# ModuleCarrier-Laird-BL652-v1_0_0.net
KiCad netlist of a schematic drawn in EAGLE
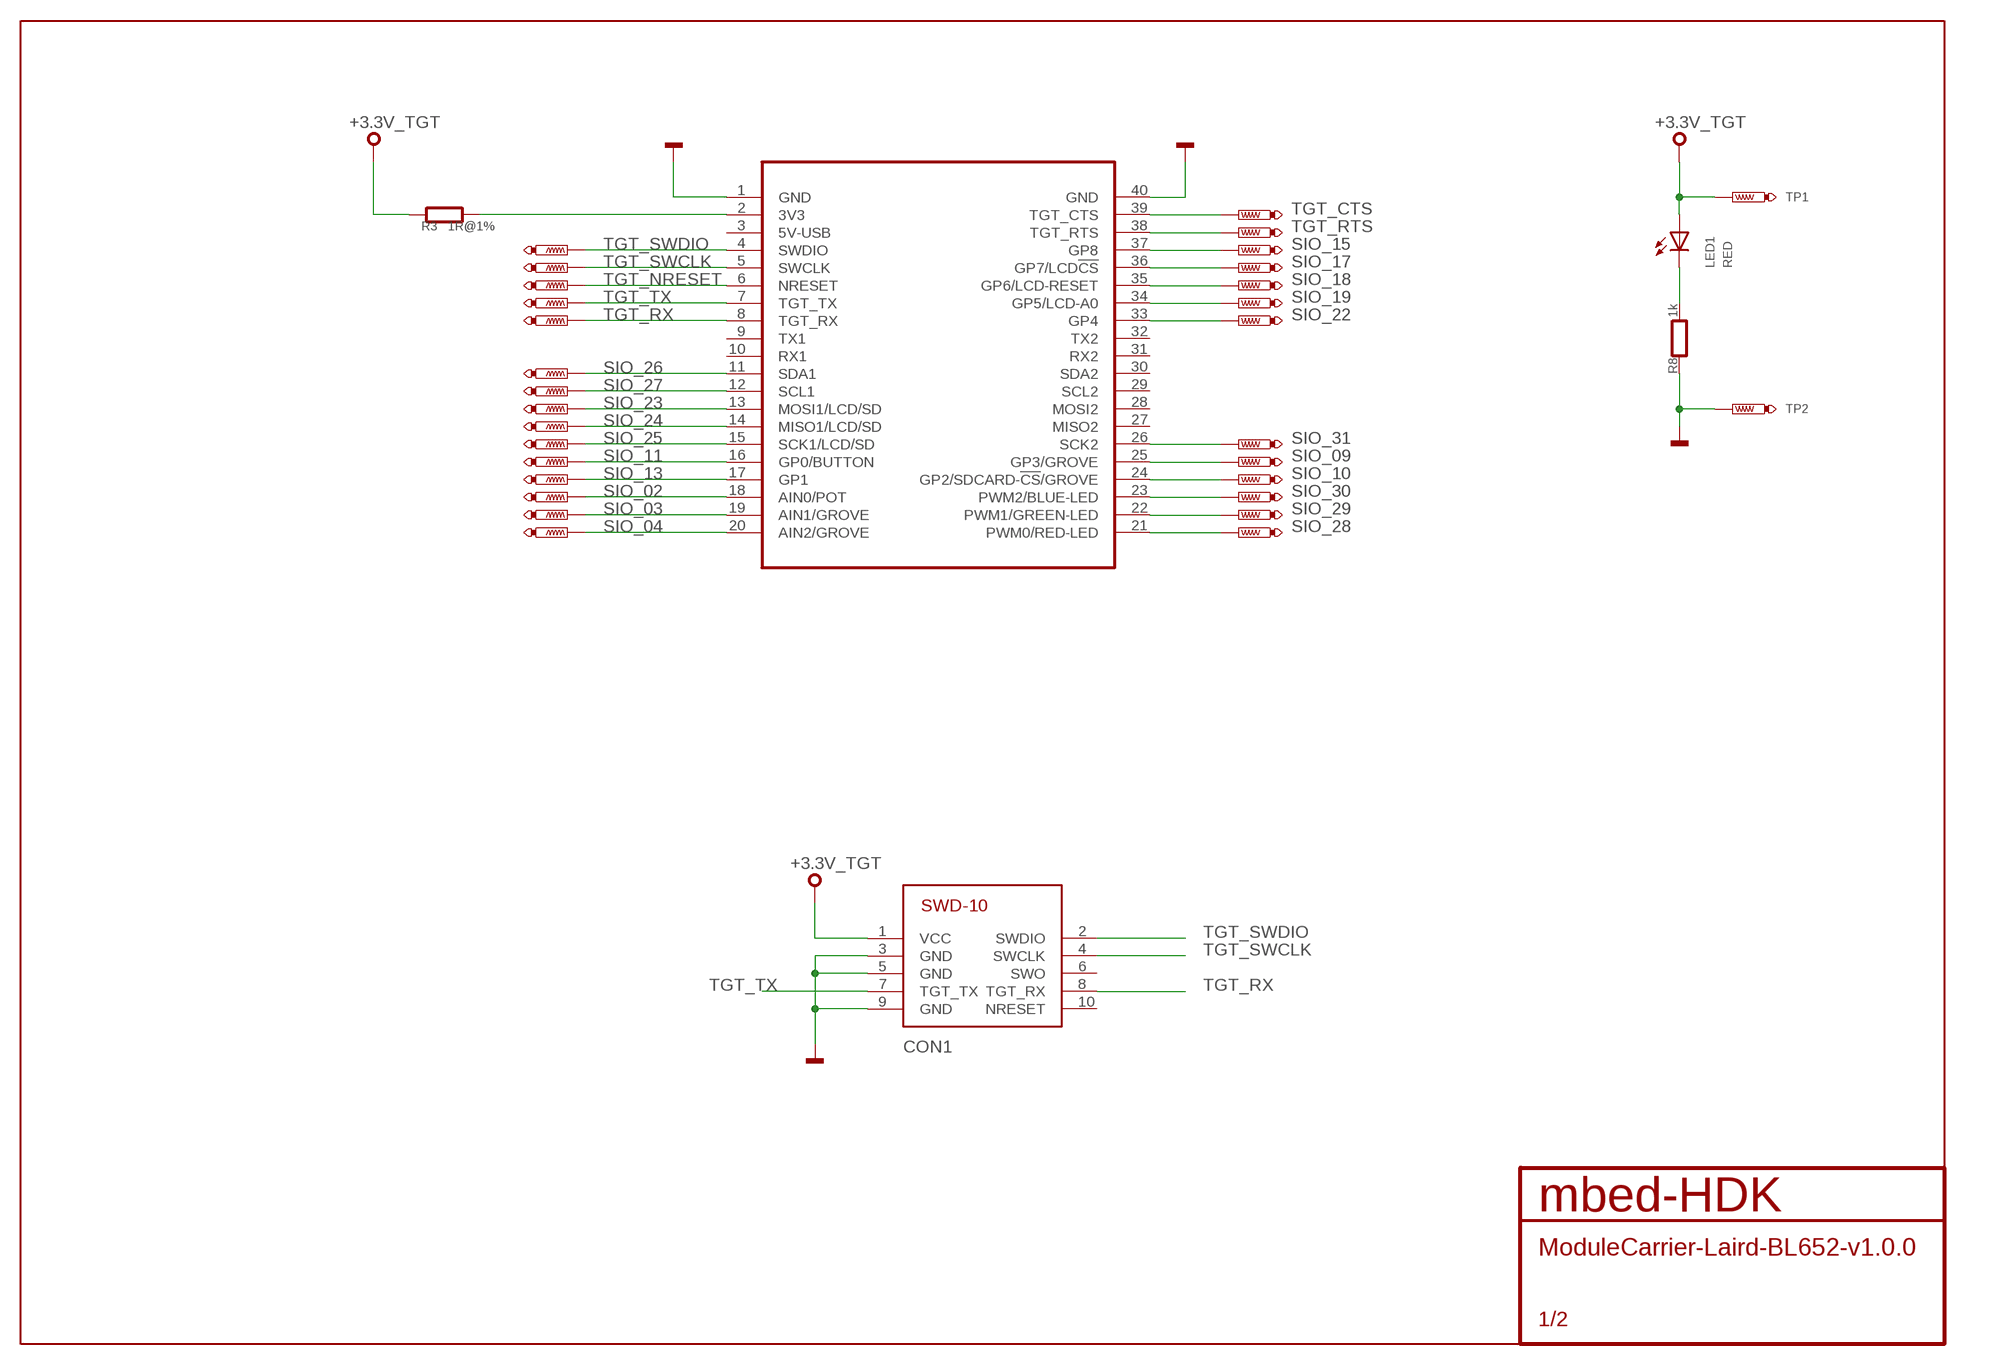
[diagram p0: schematic, sheet 1]
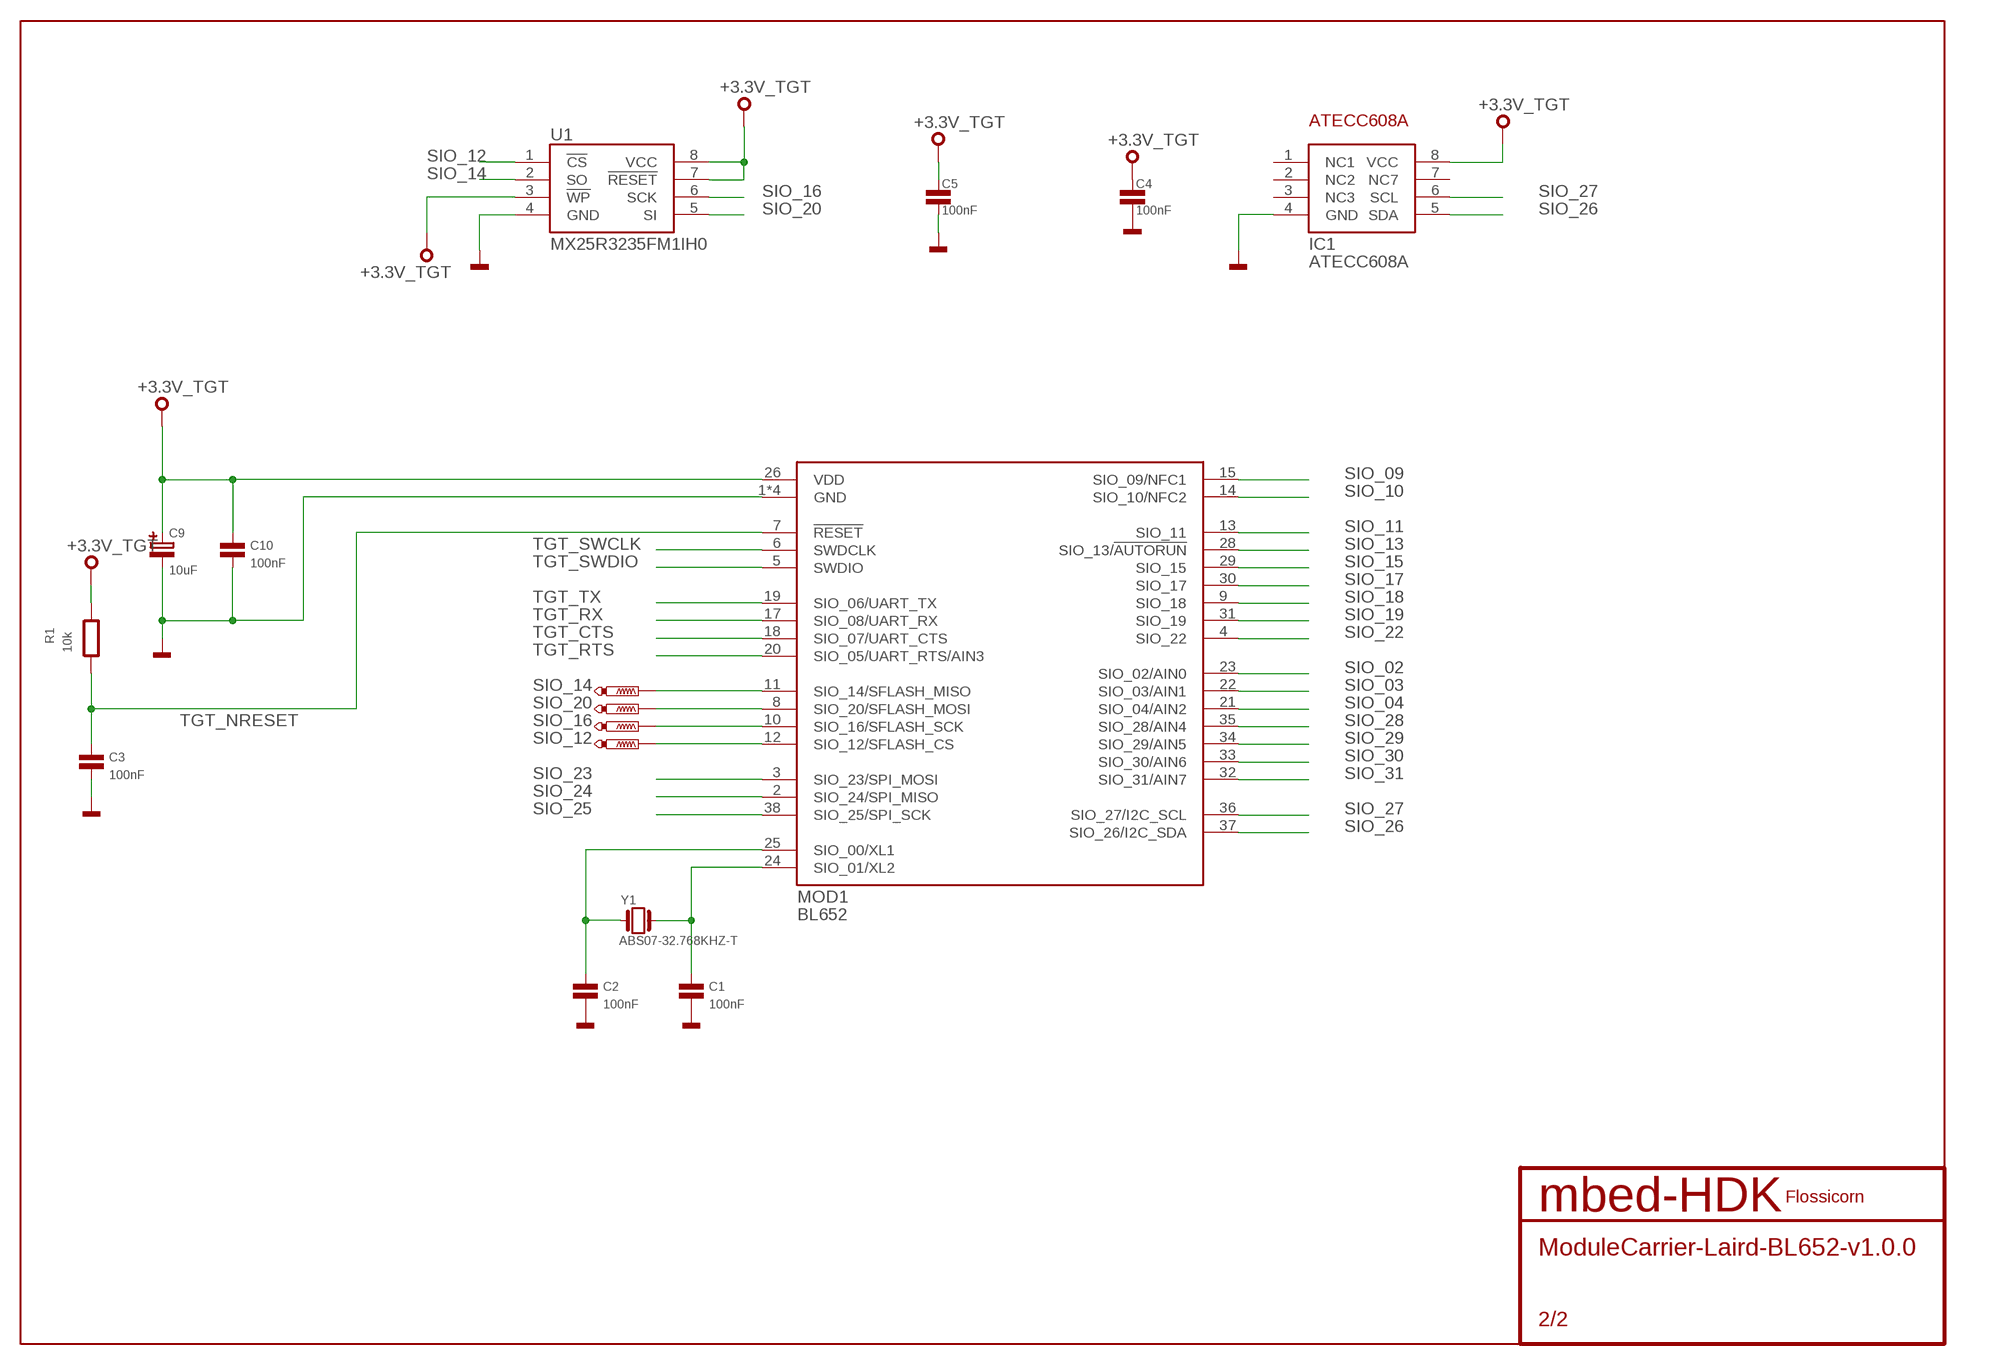
[diagram p1: schematic, sheet 2]

(export (version "E")
  (design (tool "Eeschema 10.0.6"))
  (components
    (comp (ref "CON1")
      (value "SWD-10/TC2050_SMD")
      (footprint "eagle-import:FTSH-105-02")
      (libsource (lib "eagle-import") (part "SWD-10/TC2050_SMD"))
    )
    (comp (ref "LED1")
      (value "RED")
      (footprint "eagle-import:CHIPLED_0603")
      (fields (field (name "MF") "Wurth Electronics Inc"))
      (libsource (lib "eagle-import") (part "SMD_LED0603"))
    )
    (comp (ref "MOD2")
      (value "MODULE_DAUGHTER")
      (footprint "eagle-import:MODULE_DAUGHTER")
      (libsource (lib "eagle-import") (part "MODULE_DAUGHTER"))
    )
    (comp (ref "R3")
      (value "1R@1%")
      (footprint "eagle-import:0603")
      (libsource (lib "eagle-import") (part "RESISTOR0603"))
    )
    (comp (ref "R8")
      (value "1k")
      (footprint "eagle-import:0603")
      (libsource (lib "eagle-import") (part "RESISTOR0603"))
    )
    (comp (ref "TP1")
      (value "TEST-POINT-50R-PTH")
      (footprint "eagle-import:TP50-PTH")
      (libsource (lib "eagle-import") (part "TEST-POINT-50R-PTH"))
    )
    (comp (ref "TP2")
      (value "TEST-POINT-50R-PTH")
      (footprint "eagle-import:TP50-PTH")
      (libsource (lib "eagle-import") (part "TEST-POINT-50R-PTH"))
    )
    (comp (ref "TP3")
      (value "PTR1TP07R")
      (footprint "eagle-import:TP07R")
      (libsource (lib "eagle-import") (part "PTR1TP07R"))
    )
    (comp (ref "TP4")
      (value "PTR1TP07R")
      (footprint "eagle-import:TP07R")
      (libsource (lib "eagle-import") (part "PTR1TP07R"))
    )
    (comp (ref "TP5")
      (value "PTR1TP07R")
      (footprint "eagle-import:TP07R")
      (libsource (lib "eagle-import") (part "PTR1TP07R"))
    )
    (comp (ref "TP6")
      (value "PTR1TP07R")
      (footprint "eagle-import:TP07R")
      (libsource (lib "eagle-import") (part "PTR1TP07R"))
    )
    (comp (ref "TP7")
      (value "PTR1TP07R")
      (footprint "eagle-import:TP07R")
      (libsource (lib "eagle-import") (part "PTR1TP07R"))
    )
    (comp (ref "TP8")
      (value "PTR1TP07R")
      (footprint "eagle-import:TP07R")
      (libsource (lib "eagle-import") (part "PTR1TP07R"))
    )
    (comp (ref "TP9")
      (value "PTR1TP07R")
      (footprint "eagle-import:TP07R")
      (libsource (lib "eagle-import") (part "PTR1TP07R"))
    )
    (comp (ref "TP10")
      (value "PTR1TP07R")
      (footprint "eagle-import:TP07R")
      (libsource (lib "eagle-import") (part "PTR1TP07R"))
    )
    (comp (ref "TP11")
      (value "PTR1TP07R")
      (footprint "eagle-import:TP07R")
      (libsource (lib "eagle-import") (part "PTR1TP07R"))
    )
    (comp (ref "TP12")
      (value "PTR1TP07R")
      (footprint "eagle-import:TP07R")
      (libsource (lib "eagle-import") (part "PTR1TP07R"))
    )
    (comp (ref "TP13")
      (value "PTR1TP07R")
      (footprint "eagle-import:TP07R")
      (libsource (lib "eagle-import") (part "PTR1TP07R"))
    )
    (comp (ref "TP14")
      (value "PTR1TP07R")
      (footprint "eagle-import:TP07R")
      (libsource (lib "eagle-import") (part "PTR1TP07R"))
    )
    (comp (ref "TP15")
      (value "PTR1TP07R")
      (footprint "eagle-import:TP07R")
      (libsource (lib "eagle-import") (part "PTR1TP07R"))
    )
    (comp (ref "TP16")
      (value "PTR1TP07R")
      (footprint "eagle-import:TP07R")
      (libsource (lib "eagle-import") (part "PTR1TP07R"))
    )
    (comp (ref "TP17")
      (value "PTR1TP07R")
      (footprint "eagle-import:TP07R")
      (libsource (lib "eagle-import") (part "PTR1TP07R"))
    )
    (comp (ref "TP18")
      (value "PTR1TP07R")
      (footprint "eagle-import:TP07R")
      (libsource (lib "eagle-import") (part "PTR1TP07R"))
    )
    (comp (ref "TP19")
      (value "PTR1TP07R")
      (footprint "eagle-import:TP07R")
      (libsource (lib "eagle-import") (part "PTR1TP07R"))
    )
    (comp (ref "TP20")
      (value "PTR1TP07R")
      (footprint "eagle-import:TP07R")
      (libsource (lib "eagle-import") (part "PTR1TP07R"))
    )
    (comp (ref "TP21")
      (value "PTR1TP07R")
      (footprint "eagle-import:TP07R")
      (libsource (lib "eagle-import") (part "PTR1TP07R"))
    )
    (comp (ref "TP22")
      (value "PTR1TP07R")
      (footprint "eagle-import:TP07R")
      (libsource (lib "eagle-import") (part "PTR1TP07R"))
    )
    (comp (ref "TP23")
      (value "PTR1TP07R")
      (footprint "eagle-import:TP07R")
      (libsource (lib "eagle-import") (part "PTR1TP07R"))
    )
    (comp (ref "TP24")
      (value "PTR1TP07R")
      (footprint "eagle-import:TP07R")
      (libsource (lib "eagle-import") (part "PTR1TP07R"))
    )
    (comp (ref "TP25")
      (value "PTR1TP07R")
      (footprint "eagle-import:TP07R")
      (libsource (lib "eagle-import") (part "PTR1TP07R"))
    )
    (comp (ref "TP26")
      (value "PTR1TP07R")
      (footprint "eagle-import:TP07R")
      (libsource (lib "eagle-import") (part "PTR1TP07R"))
    )
    (comp (ref "TP27")
      (value "PTR1TP07R")
      (footprint "eagle-import:TP07R")
      (libsource (lib "eagle-import") (part "PTR1TP07R"))
    )
    (comp (ref "TP28")
      (value "PTR1TP07R")
      (footprint "eagle-import:TP07R")
      (libsource (lib "eagle-import") (part "PTR1TP07R"))
    )
    (comp (ref "TP29")
      (value "PTR1TP07R")
      (footprint "eagle-import:TP07R")
      (libsource (lib "eagle-import") (part "PTR1TP07R"))
    )
    (comp (ref "TP30")
      (value "PTR1TP07R")
      (footprint "eagle-import:TP07R")
      (libsource (lib "eagle-import") (part "PTR1TP07R"))
    )
    (comp (ref "C1")
      (value "100nF")
      (footprint "eagle-import:0603")
      (libsource (lib "eagle-import") (part "C0603"))
    )
    (comp (ref "C2")
      (value "100nF")
      (footprint "eagle-import:0603")
      (libsource (lib "eagle-import") (part "C0603"))
    )
    (comp (ref "C3")
      (value "100nF")
      (footprint "eagle-import:0603")
      (libsource (lib "eagle-import") (part "C0603"))
    )
    (comp (ref "C4")
      (value "100nF")
      (footprint "eagle-import:0603")
      (libsource (lib "eagle-import") (part "CAPACITOR0603"))
    )
    (comp (ref "C5")
      (value "100nF")
      (footprint "eagle-import:0603")
      (libsource (lib "eagle-import") (part "CAPACITOR0603"))
    )
    (comp (ref "C9")
      (value "10uF")
      (footprint "eagle-import:CASE-B")
      (libsource (lib "eagle-import") (part "C-POLB"))
    )
    (comp (ref "C10")
      (value "100nF")
      (footprint "eagle-import:0603")
      (libsource (lib "eagle-import") (part "C0603"))
    )
    (comp (ref "IC1")
      (value "ATECC608A")
      (footprint "eagle-import:SO8")
      (libsource (lib "eagle-import") (part "ATECC608A"))
    )
    (comp (ref "MOD1")
      (value "BL652")
      (footprint "eagle-import:BL652")
      (libsource (lib "eagle-import") (part "BL652"))
    )
    (comp (ref "R1")
      (value "10k")
      (footprint "eagle-import:0603")
      (libsource (lib "eagle-import") (part "RESISTOR0603"))
    )
    (comp (ref "SS1")
      (value "FLOSSICORN0.25")
      (footprint "eagle-import:FLOSSICORN-0.25")
      (libsource (lib "eagle-import") (part "FLOSSICORN0.25"))
    )
    (comp (ref "TP31")
      (value "PTR1TP07R")
      (footprint "eagle-import:TP07R")
      (libsource (lib "eagle-import") (part "PTR1TP07R"))
    )
    (comp (ref "TP32")
      (value "PTR1TP07R")
      (footprint "eagle-import:TP07R")
      (libsource (lib "eagle-import") (part "PTR1TP07R"))
    )
    (comp (ref "TP33")
      (value "PTR1TP07R")
      (footprint "eagle-import:TP07R")
      (libsource (lib "eagle-import") (part "PTR1TP07R"))
    )
    (comp (ref "TP34")
      (value "PTR1TP07R")
      (footprint "eagle-import:TP07R")
      (libsource (lib "eagle-import") (part "PTR1TP07R"))
    )
    (comp (ref "U1")
      (value "MX25R3235FM1IH0")
      (footprint "eagle-import:SO8")
      (fields (field (name "MF") "Macronix"))
      (libsource (lib "eagle-import") (part "MX25R3235FM1IH0"))
    )
    (comp (ref "Y1")
      (value "ABS07-32.768KHZ-T")
      (footprint "eagle-import:FC135")
      (fields (field (name "MF") "Abracon"))
      (libsource (lib "eagle-import") (part "ABS07-32.768KHZ-T"))
    )
  )
  (nets
    (net (code "1") (name "+3.3V_TGT") (class "Default")
      (node (ref "C10") (pin "1") (pinfunction "P$1_1") (pintype "passive"))
      (node (ref "C4") (pin "1") (pinfunction "P$1_1") (pintype "passive"))
      (node (ref "C5") (pin "1") (pinfunction "P$1_1") (pintype "passive"))
      (node (ref "C9") (pin "1") (pinfunction "1_1") (pintype "passive"))
      (node (ref "CON1") (pin "1") (pinfunction "VCC_1") (pintype "bidirectional"))
      (node (ref "IC1") (pin "8") (pinfunction "VCC_8") (pintype "bidirectional"))
      (node (ref "LED1") (pin "A") (pinfunction "A_A") (pintype "passive"))
      (node (ref "MOD1") (pin "26") (pinfunction "VDD_26") (pintype "bidirectional"))
      (node (ref "R1") (pin "2") (pinfunction "P$2_2") (pintype "passive"))
      (node (ref "R3") (pin "1") (pinfunction "P$1_1") (pintype "passive"))
      (node (ref "TP1") (pin "TP") (pinfunction "TP_TP") (pintype "input"))
      (node (ref "U1") (pin "3") (pinfunction "~{WP}_3") (pintype "bidirectional"))
      (node (ref "U1") (pin "7") (pinfunction "~{RESET}_7") (pintype "bidirectional"))
      (node (ref "U1") (pin "8") (pinfunction "VCC_8") (pintype "bidirectional"))
    )
    (net (code "2") (name "GND") (class "Default")
      (node (ref "C1") (pin "2") (pinfunction "P$2_2") (pintype "passive"))
      (node (ref "C10") (pin "2") (pinfunction "P$2_2") (pintype "passive"))
      (node (ref "C2") (pin "2") (pinfunction "P$2_2") (pintype "passive"))
      (node (ref "C3") (pin "2") (pinfunction "P$2_2") (pintype "passive"))
      (node (ref "C4") (pin "2") (pinfunction "P$2_2") (pintype "passive"))
      (node (ref "C5") (pin "2") (pinfunction "P$2_2") (pintype "passive"))
      (node (ref "C9") (pin "2") (pinfunction "2_2") (pintype "passive"))
      (node (ref "CON1") (pin "3") (pinfunction "GND_3") (pintype "bidirectional"))
      (node (ref "CON1") (pin "5") (pinfunction "GND_5") (pintype "bidirectional"))
      (node (ref "CON1") (pin "9") (pinfunction "GND_9") (pintype "bidirectional"))
      (node (ref "IC1") (pin "4") (pinfunction "GND_4") (pintype "bidirectional"))
      (node (ref "MOD1") (pin "1") (pinfunction "GND_1") (pintype "bidirectional"))
      (node (ref "MOD1") (pin "16") (pinfunction "GND_16") (pintype "bidirectional"))
      (node (ref "MOD1") (pin "27") (pinfunction "GND_27") (pintype "bidirectional"))
      (node (ref "MOD1") (pin "39") (pinfunction "GND_39") (pintype "bidirectional"))
      (node (ref "MOD2") (pin "1") (pinfunction "GND_1") (pintype "bidirectional"))
      (node (ref "MOD2") (pin "40") (pinfunction "GND_40") (pintype "bidirectional"))
      (node (ref "R8") (pin "1") (pinfunction "P$1_1") (pintype "passive"))
      (node (ref "TP2") (pin "TP") (pinfunction "TP_TP") (pintype "input"))
      (node (ref "U1") (pin "4") (pinfunction "GND_4") (pintype "bidirectional"))
    )
    (net (code "3") (name "Net-(C1-P$1)") (class "Default")
      (node (ref "C1") (pin "1") (pinfunction "P$1_1") (pintype "passive"))
      (node (ref "MOD1") (pin "24") (pinfunction "SIO_01/XL2_24") (pintype "bidirectional"))
      (node (ref "Y1") (pin "X2") (pinfunction "2_X2") (pintype "passive"))
    )
    (net (code "4") (name "Net-(C2-P$1)") (class "Default")
      (node (ref "C2") (pin "1") (pinfunction "P$1_1") (pintype "passive"))
      (node (ref "MOD1") (pin "25") (pinfunction "SIO_00/XL1_25") (pintype "bidirectional"))
      (node (ref "Y1") (pin "X1") (pinfunction "1_X1") (pintype "passive"))
    )
    (net (code "5") (name "Net-(MOD2-3V3)") (class "Default")
      (node (ref "MOD2") (pin "2") (pinfunction "3V3_2") (pintype "bidirectional"))
      (node (ref "R3") (pin "2") (pinfunction "P$2_2") (pintype "passive"))
    )
    (net (code "6") (name "Net-(R8-P$2)") (class "Default")
      (node (ref "LED1") (pin "C") (pinfunction "C_C") (pintype "passive"))
      (node (ref "R8") (pin "2") (pinfunction "P$2_2") (pintype "passive"))
    )
    (net (code "7") (name "SIO_02") (class "Default")
      (node (ref "MOD1") (pin "23") (pinfunction "SIO_02/AIN0_23") (pintype "bidirectional"))
      (node (ref "MOD2") (pin "18") (pinfunction "AIN0/POT_18") (pintype "bidirectional"))
      (node (ref "TP10") (pin "TP") (pinfunction "TP_TP") (pintype "input"))
    )
    (net (code "8") (name "SIO_03") (class "Default")
      (node (ref "MOD1") (pin "22") (pinfunction "SIO_03/AIN1_22") (pintype "bidirectional"))
      (node (ref "MOD2") (pin "19") (pinfunction "AIN1/GROVE_19") (pintype "bidirectional"))
      (node (ref "TP11") (pin "TP") (pinfunction "TP_TP") (pintype "input"))
    )
    (net (code "9") (name "SIO_04") (class "Default")
      (node (ref "MOD1") (pin "21") (pinfunction "SIO_04/AIN2_21") (pintype "bidirectional"))
      (node (ref "MOD2") (pin "20") (pinfunction "AIN2/GROVE_20") (pintype "bidirectional"))
      (node (ref "TP12") (pin "TP") (pinfunction "TP_TP") (pintype "input"))
    )
    (net (code "10") (name "SIO_09") (class "Default")
      (node (ref "MOD1") (pin "15") (pinfunction "SIO_09/NFC1_15") (pintype "bidirectional"))
      (node (ref "MOD2") (pin "25") (pinfunction "GP3/GROVE_25") (pintype "bidirectional"))
      (node (ref "TP17") (pin "TP") (pinfunction "TP_TP") (pintype "input"))
    )
    (net (code "11") (name "SIO_10") (class "Default")
      (node (ref "MOD1") (pin "14") (pinfunction "SIO_10/NFC2_14") (pintype "bidirectional"))
      (node (ref "MOD2") (pin "24") (pinfunction "GP2/SDCARD-~{CS}/GROVE_24") (pintype "bidirectional"))
      (node (ref "TP16") (pin "TP") (pinfunction "TP_TP") (pintype "input"))
    )
    (net (code "12") (name "SIO_11") (class "Default")
      (node (ref "MOD1") (pin "13") (pinfunction "SIO_11_13") (pintype "bidirectional"))
      (node (ref "MOD2") (pin "16") (pinfunction "GP0/BUTTON_16") (pintype "bidirectional"))
      (node (ref "TP8") (pin "TP") (pinfunction "TP_TP") (pintype "input"))
    )
    (net (code "13") (name "SIO_12") (class "Default")
      (node (ref "MOD1") (pin "12") (pinfunction "SIO_12/SFLASH_CS_12") (pintype "bidirectional"))
      (node (ref "TP34") (pin "TP") (pinfunction "TP_TP") (pintype "input"))
      (node (ref "U1") (pin "1") (pinfunction "~{CS}_1") (pintype "bidirectional"))
    )
    (net (code "14") (name "SIO_13") (class "Default")
      (node (ref "MOD1") (pin "28") (pinfunction "SIO_13/~{AUTORUN}_28") (pintype "bidirectional"))
      (node (ref "MOD2") (pin "17") (pinfunction "GP1_17") (pintype "bidirectional"))
      (node (ref "TP9") (pin "TP") (pinfunction "TP_TP") (pintype "input"))
    )
    (net (code "15") (name "SIO_14") (class "Default")
      (node (ref "MOD1") (pin "11") (pinfunction "SIO_14/SFLASH_MISO_11") (pintype "bidirectional"))
      (node (ref "TP31") (pin "TP") (pinfunction "TP_TP") (pintype "input"))
      (node (ref "U1") (pin "2") (pinfunction "SO_2") (pintype "bidirectional"))
    )
    (net (code "16") (name "SIO_15") (class "Default")
      (node (ref "MOD1") (pin "29") (pinfunction "SIO_15_29") (pintype "bidirectional"))
      (node (ref "MOD2") (pin "37") (pinfunction "GP8_37") (pintype "bidirectional"))
      (node (ref "TP22") (pin "TP") (pinfunction "TP_TP") (pintype "input"))
    )
    (net (code "17") (name "SIO_16") (class "Default")
      (node (ref "MOD1") (pin "10") (pinfunction "SIO_16/SFLASH_SCK_10") (pintype "bidirectional"))
      (node (ref "TP33") (pin "TP") (pinfunction "TP_TP") (pintype "input"))
      (node (ref "U1") (pin "6") (pinfunction "SCK_6") (pintype "bidirectional"))
    )
    (net (code "18") (name "SIO_17") (class "Default")
      (node (ref "MOD1") (pin "30") (pinfunction "SIO_17_30") (pintype "bidirectional"))
      (node (ref "MOD2") (pin "36") (pinfunction "GP7/LCD~{CS}_36") (pintype "bidirectional"))
      (node (ref "TP21") (pin "TP") (pinfunction "TP_TP") (pintype "input"))
    )
    (net (code "19") (name "SIO_18") (class "Default")
      (node (ref "MOD1") (pin "9") (pinfunction "SIO_18_9") (pintype "bidirectional"))
      (node (ref "MOD2") (pin "35") (pinfunction "GP6/LCD-RESET_35") (pintype "bidirectional"))
      (node (ref "TP20") (pin "TP") (pinfunction "TP_TP") (pintype "input"))
    )
    (net (code "20") (name "SIO_19") (class "Default")
      (node (ref "MOD1") (pin "31") (pinfunction "SIO_19_31") (pintype "bidirectional"))
      (node (ref "MOD2") (pin "34") (pinfunction "GP5/LCD-A0_34") (pintype "bidirectional"))
      (node (ref "TP19") (pin "TP") (pinfunction "TP_TP") (pintype "input"))
    )
    (net (code "21") (name "SIO_20") (class "Default")
      (node (ref "MOD1") (pin "8") (pinfunction "SIO_20/SFLASH_MOSI_8") (pintype "bidirectional"))
      (node (ref "TP32") (pin "TP") (pinfunction "TP_TP") (pintype "input"))
      (node (ref "U1") (pin "5") (pinfunction "SI_5") (pintype "bidirectional"))
    )
    (net (code "22") (name "SIO_22") (class "Default")
      (node (ref "MOD1") (pin "4") (pinfunction "SIO_22_4") (pintype "bidirectional"))
      (node (ref "MOD2") (pin "33") (pinfunction "GP4_33") (pintype "bidirectional"))
      (node (ref "TP18") (pin "TP") (pinfunction "TP_TP") (pintype "input"))
    )
    (net (code "23") (name "SIO_23") (class "Default")
      (node (ref "MOD1") (pin "3") (pinfunction "SIO_23/SPI_MOSI_3") (pintype "bidirectional"))
      (node (ref "MOD2") (pin "13") (pinfunction "MOSI1/LCD/SD_13") (pintype "bidirectional"))
      (node (ref "TP5") (pin "TP") (pinfunction "TP_TP") (pintype "input"))
    )
    (net (code "24") (name "SIO_24") (class "Default")
      (node (ref "MOD1") (pin "2") (pinfunction "SIO_24/SPI_MISO_2") (pintype "bidirectional"))
      (node (ref "MOD2") (pin "14") (pinfunction "MISO1/LCD/SD_14") (pintype "bidirectional"))
      (node (ref "TP6") (pin "TP") (pinfunction "TP_TP") (pintype "input"))
    )
    (net (code "25") (name "SIO_25") (class "Default")
      (node (ref "MOD1") (pin "38") (pinfunction "SIO_25/SPI_SCK_38") (pintype "bidirectional"))
      (node (ref "MOD2") (pin "15") (pinfunction "SCK1/LCD/SD_15") (pintype "bidirectional"))
      (node (ref "TP7") (pin "TP") (pinfunction "TP_TP") (pintype "input"))
    )
    (net (code "26") (name "SIO_26") (class "Default")
      (node (ref "IC1") (pin "5") (pinfunction "SDA_5") (pintype "bidirectional"))
      (node (ref "MOD1") (pin "37") (pinfunction "SIO_26/I2C_SDA_37") (pintype "bidirectional"))
      (node (ref "MOD2") (pin "11") (pinfunction "SDA1_11") (pintype "bidirectional"))
      (node (ref "TP3") (pin "TP") (pinfunction "TP_TP") (pintype "input"))
    )
    (net (code "27") (name "SIO_27") (class "Default")
      (node (ref "IC1") (pin "6") (pinfunction "SCL_6") (pintype "bidirectional"))
      (node (ref "MOD1") (pin "36") (pinfunction "SIO_27/I2C_SCL_36") (pintype "bidirectional"))
      (node (ref "MOD2") (pin "12") (pinfunction "SCL1_12") (pintype "bidirectional"))
      (node (ref "TP4") (pin "TP") (pinfunction "TP_TP") (pintype "input"))
    )
    (net (code "28") (name "SIO_28") (class "Default")
      (node (ref "MOD1") (pin "35") (pinfunction "SIO_28/AIN4_35") (pintype "bidirectional"))
      (node (ref "MOD2") (pin "21") (pinfunction "PWM0/RED-LED_21") (pintype "bidirectional"))
      (node (ref "TP13") (pin "TP") (pinfunction "TP_TP") (pintype "input"))
    )
    (net (code "29") (name "SIO_29") (class "Default")
      (node (ref "MOD1") (pin "34") (pinfunction "SIO_29/AIN5_34") (pintype "bidirectional"))
      (node (ref "MOD2") (pin "22") (pinfunction "PWM1/GREEN-LED_22") (pintype "bidirectional"))
      (node (ref "TP14") (pin "TP") (pinfunction "TP_TP") (pintype "input"))
    )
    (net (code "30") (name "SIO_30") (class "Default")
      (node (ref "MOD1") (pin "33") (pinfunction "SIO_30/AIN6_33") (pintype "bidirectional"))
      (node (ref "MOD2") (pin "23") (pinfunction "PWM2/BLUE-LED_23") (pintype "bidirectional"))
      (node (ref "TP15") (pin "TP") (pinfunction "TP_TP") (pintype "input"))
    )
    (net (code "31") (name "SIO_31") (class "Default")
      (node (ref "MOD1") (pin "32") (pinfunction "SIO_31/AIN7_32") (pintype "bidirectional"))
      (node (ref "MOD2") (pin "26") (pinfunction "SCK2_26") (pintype "bidirectional"))
      (node (ref "TP25") (pin "TP") (pinfunction "TP_TP") (pintype "input"))
    )
    (net (code "32") (name "TGT_CTS") (class "Default")
      (node (ref "MOD1") (pin "18") (pinfunction "SIO_07/UART_CTS_18") (pintype "bidirectional"))
      (node (ref "MOD2") (pin "39") (pinfunction "TGT_CTS_39") (pintype "bidirectional"))
      (node (ref "TP24") (pin "TP") (pinfunction "TP_TP") (pintype "input"))
    )
    (net (code "33") (name "TGT_NRESET") (class "Default")
      (node (ref "C3") (pin "1") (pinfunction "P$1_1") (pintype "passive"))
      (node (ref "MOD1") (pin "7") (pinfunction "~{RESET}_7") (pintype "bidirectional"))
      (node (ref "MOD2") (pin "6") (pinfunction "NRESET_6") (pintype "bidirectional"))
      (node (ref "R1") (pin "1") (pinfunction "P$1_1") (pintype "passive"))
      (node (ref "TP28") (pin "TP") (pinfunction "TP_TP") (pintype "input"))
    )
    (net (code "34") (name "TGT_RTS") (class "Default")
      (node (ref "MOD1") (pin "20") (pinfunction "SIO_05/UART_RTS/AIN3_20") (pintype "bidirectional"))
      (node (ref "MOD2") (pin "38") (pinfunction "TGT_RTS_38") (pintype "bidirectional"))
      (node (ref "TP23") (pin "TP") (pinfunction "TP_TP") (pintype "input"))
    )
    (net (code "35") (name "TGT_RX") (class "Default")
      (node (ref "CON1") (pin "8") (pinfunction "TGT_RX_8") (pintype "bidirectional"))
      (node (ref "MOD1") (pin "17") (pinfunction "SIO_08/UART_RX_17") (pintype "bidirectional"))
      (node (ref "MOD2") (pin "8") (pinfunction "TGT_RX_8") (pintype "bidirectional"))
      (node (ref "TP30") (pin "TP") (pinfunction "TP_TP") (pintype "input"))
    )
    (net (code "36") (name "TGT_SWCLK") (class "Default")
      (node (ref "CON1") (pin "4") (pinfunction "SWCLK_4") (pintype "bidirectional"))
      (node (ref "MOD1") (pin "6") (pinfunction "SWDCLK_6") (pintype "bidirectional"))
      (node (ref "MOD2") (pin "5") (pinfunction "SWCLK_5") (pintype "bidirectional"))
      (node (ref "TP27") (pin "TP") (pinfunction "TP_TP") (pintype "input"))
    )
    (net (code "37") (name "TGT_SWDIO") (class "Default")
      (node (ref "CON1") (pin "2") (pinfunction "SWDIO_2") (pintype "bidirectional"))
      (node (ref "MOD1") (pin "5") (pinfunction "SWDIO_5") (pintype "bidirectional"))
      (node (ref "MOD2") (pin "4") (pinfunction "SWDIO_4") (pintype "bidirectional"))
      (node (ref "TP26") (pin "TP") (pinfunction "TP_TP") (pintype "input"))
    )
    (net (code "38") (name "TGT_TX") (class "Default")
      (node (ref "CON1") (pin "7") (pinfunction "TGT_TX_7") (pintype "bidirectional"))
      (node (ref "MOD1") (pin "19") (pinfunction "SIO_06/UART_TX_19") (pintype "bidirectional"))
      (node (ref "MOD2") (pin "7") (pinfunction "TGT_TX_7") (pintype "bidirectional"))
      (node (ref "TP29") (pin "TP") (pinfunction "TP_TP") (pintype "input"))
    )
    (net (code "39") (name "unconnected-(CON1-NRESET-Pad10)") (class "Default")
      (node (ref "CON1") (pin "10") (pinfunction "NRESET_10") (pintype "bidirectional"))
    )
    (net (code "40") (name "unconnected-(CON1-SWO-Pad6)") (class "Default")
      (node (ref "CON1") (pin "6") (pinfunction "SWO_6") (pintype "bidirectional"))
    )
    (net (code "41") (name "unconnected-(IC1-NC1-Pad1)") (class "Default")
      (node (ref "IC1") (pin "1") (pinfunction "NC1_1") (pintype "bidirectional"))
    )
    (net (code "42") (name "unconnected-(IC1-NC2-Pad2)") (class "Default")
      (node (ref "IC1") (pin "2") (pinfunction "NC2_2") (pintype "bidirectional"))
    )
    (net (code "43") (name "unconnected-(IC1-NC3-Pad3)") (class "Default")
      (node (ref "IC1") (pin "3") (pinfunction "NC3_3") (pintype "bidirectional"))
    )
    (net (code "44") (name "unconnected-(IC1-NC7-Pad7)") (class "Default")
      (node (ref "IC1") (pin "7") (pinfunction "NC7_7") (pintype "bidirectional"))
    )
    (net (code "45") (name "unconnected-(MOD2-5V-USB-Pad3)") (class "Default")
      (node (ref "MOD2") (pin "3") (pinfunction "5V-USB_3") (pintype "bidirectional"))
    )
    (net (code "46") (name "unconnected-(MOD2-MISO2-Pad27)") (class "Default")
      (node (ref "MOD2") (pin "27") (pinfunction "MISO2_27") (pintype "bidirectional"))
    )
    (net (code "47") (name "unconnected-(MOD2-MOSI2-Pad28)") (class "Default")
      (node (ref "MOD2") (pin "28") (pinfunction "MOSI2_28") (pintype "bidirectional"))
    )
    (net (code "48") (name "unconnected-(MOD2-RX1-Pad10)") (class "Default")
      (node (ref "MOD2") (pin "10") (pinfunction "RX1_10") (pintype "bidirectional"))
    )
    (net (code "49") (name "unconnected-(MOD2-RX2-Pad31)") (class "Default")
      (node (ref "MOD2") (pin "31") (pinfunction "RX2_31") (pintype "bidirectional"))
    )
    (net (code "50") (name "unconnected-(MOD2-SCL2-Pad29)") (class "Default")
      (node (ref "MOD2") (pin "29") (pinfunction "SCL2_29") (pintype "bidirectional"))
    )
    (net (code "51") (name "unconnected-(MOD2-SDA2-Pad30)") (class "Default")
      (node (ref "MOD2") (pin "30") (pinfunction "SDA2_30") (pintype "bidirectional"))
    )
    (net (code "52") (name "unconnected-(MOD2-TX1-Pad9)") (class "Default")
      (node (ref "MOD2") (pin "9") (pinfunction "TX1_9") (pintype "bidirectional"))
    )
    (net (code "53") (name "unconnected-(MOD2-TX2-Pad32)") (class "Default")
      (node (ref "MOD2") (pin "32") (pinfunction "TX2_32") (pintype "bidirectional"))
    )
  )
)
